# Memory.net
KiCad netlist of a schematic drawn in Altium Designer
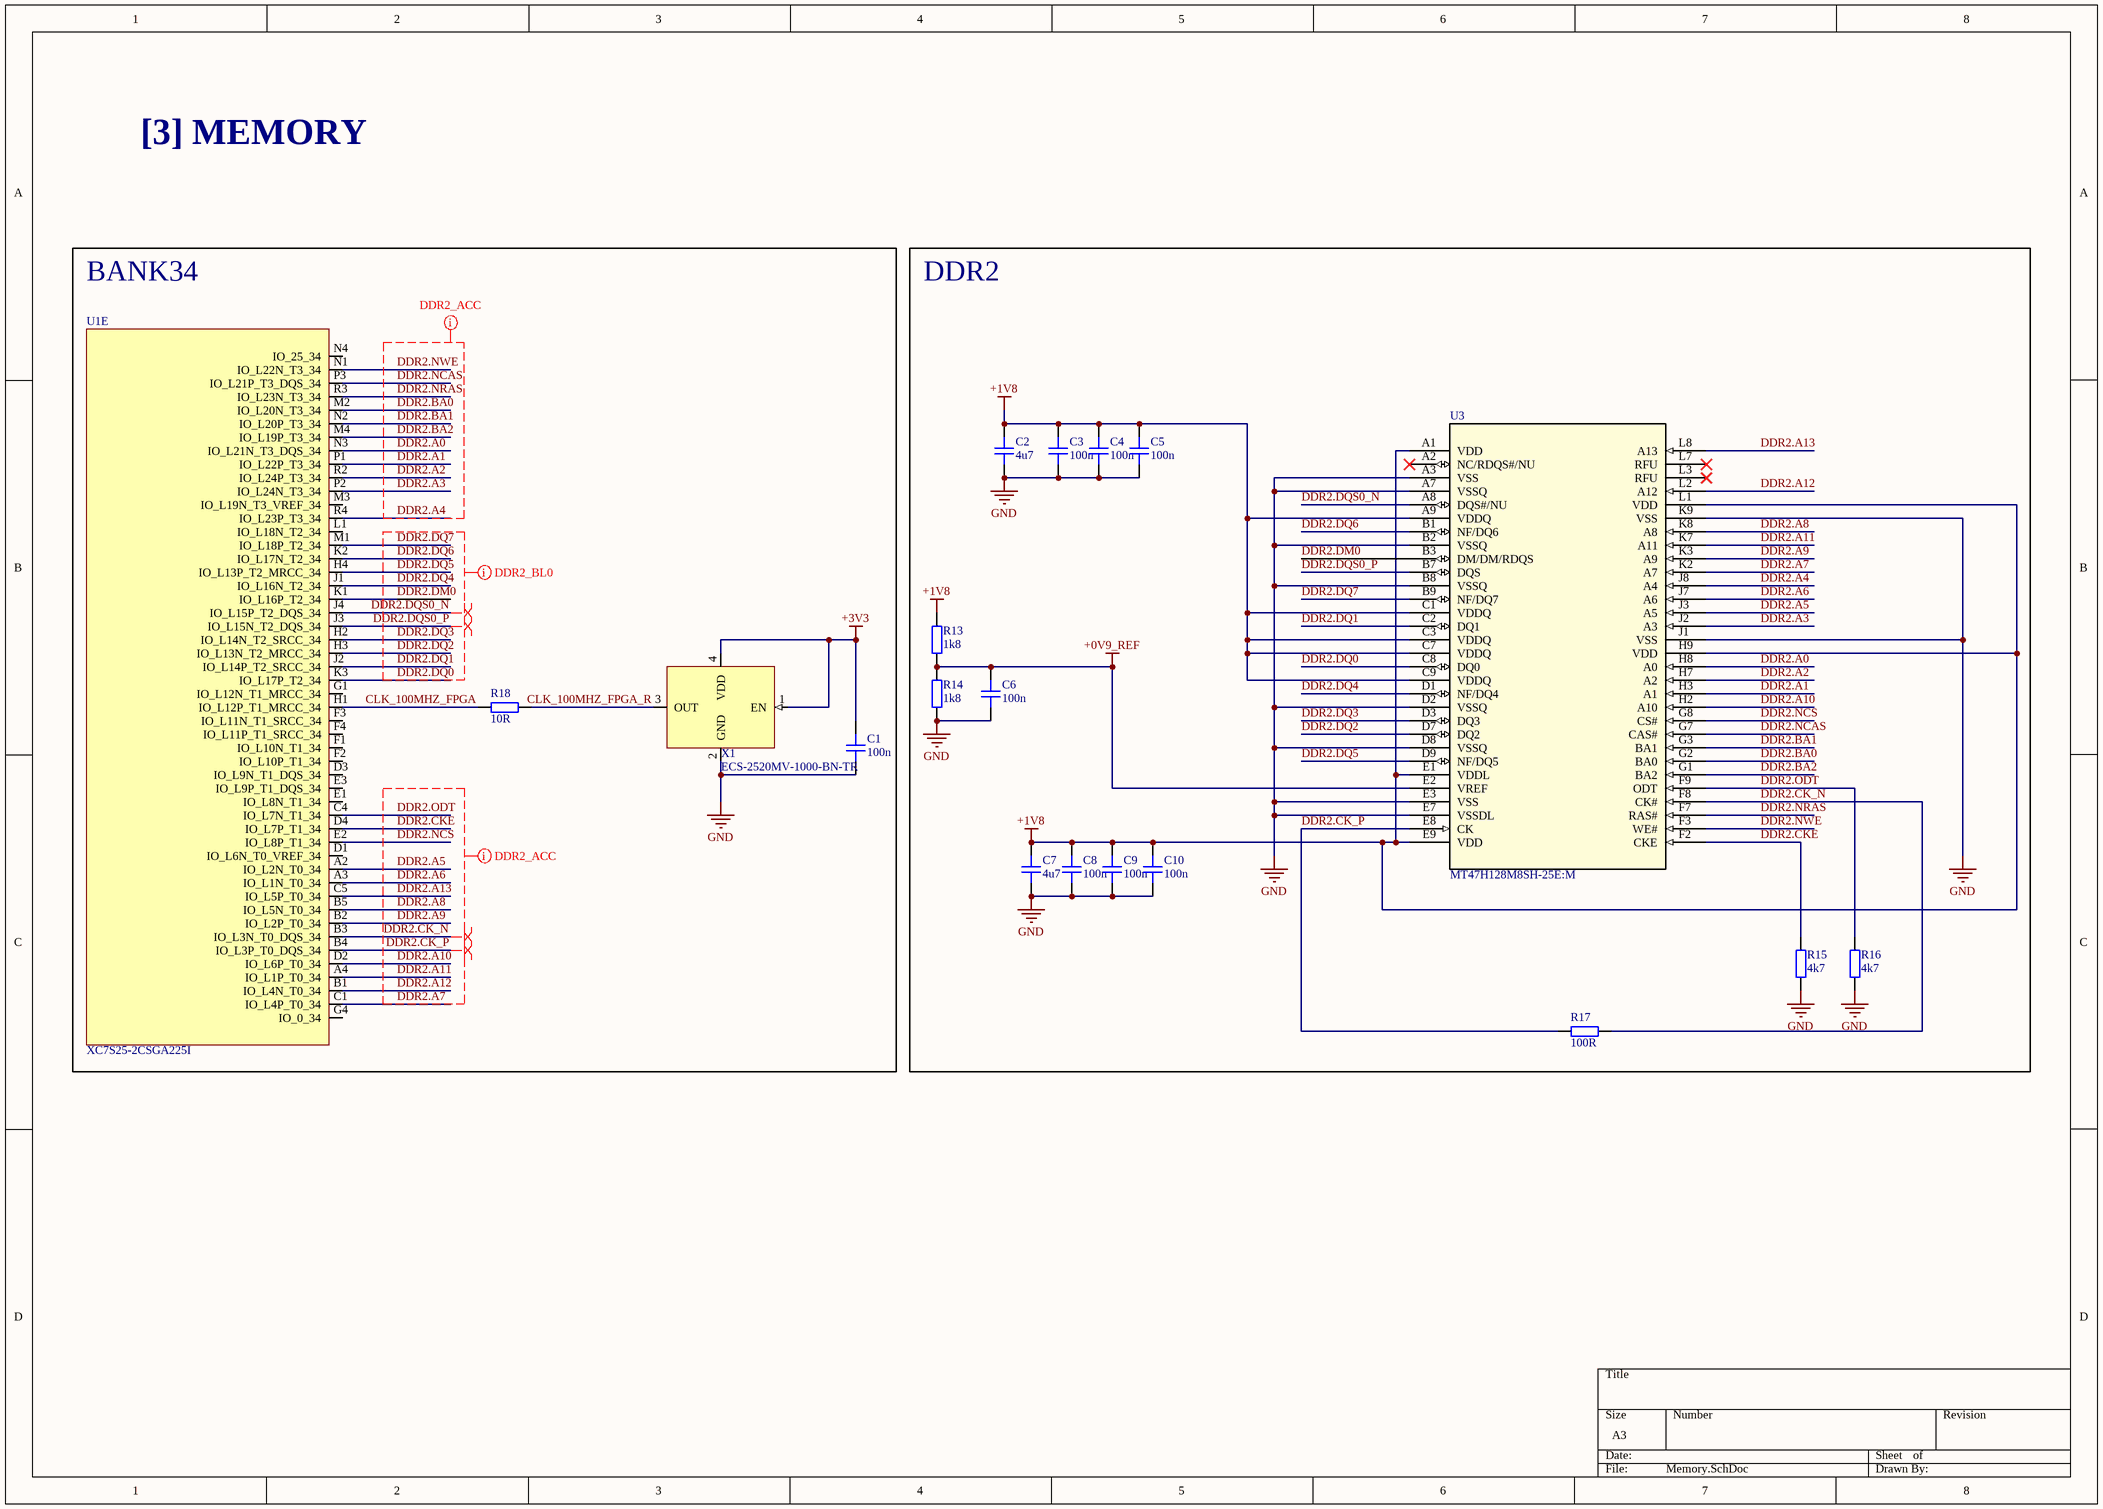
[diagram p0: Memory.SchDoc]

(export (version "E")
  (design (tool "Eeschema 10.0.6"))
  (components
    (comp (ref "C1")
      (value "100n")
      (footprint "CAP_0402")
      (description "Capacitor SMD 0402")
      (libsource (lib "Schematic-Lib-PhilsLab") (part "CAP_0402"))
    )
    (comp (ref "C2")
      (value "4u7")
      (footprint "CAP_0402")
      (description "Capacitor SMD 0402")
      (libsource (lib "Schematic-Lib-PhilsLab") (part "CAP_0402"))
    )
    (comp (ref "C3")
      (value "100n")
      (footprint "CAP_0402")
      (description "Capacitor SMD 0402")
      (libsource (lib "Schematic-Lib-PhilsLab") (part "CAP_0402"))
    )
    (comp (ref "C4")
      (value "100n")
      (footprint "CAP_0402")
      (description "Capacitor SMD 0402")
      (libsource (lib "Schematic-Lib-PhilsLab") (part "CAP_0402"))
    )
    (comp (ref "C5")
      (value "100n")
      (footprint "CAP_0402")
      (description "Capacitor SMD 0402")
      (libsource (lib "Schematic-Lib-PhilsLab") (part "CAP_0402"))
    )
    (comp (ref "C6")
      (value "100n")
      (footprint "CAP_0201")
      (description "Capacitor SMD 0201")
      (libsource (lib "Schematic-Lib-PhilsLab") (part "CAP_0201"))
    )
    (comp (ref "C7")
      (value "4u7")
      (footprint "CAP_0402")
      (description "Capacitor SMD 0402")
      (libsource (lib "Schematic-Lib-PhilsLab") (part "CAP_0402"))
    )
    (comp (ref "C8")
      (value "100n")
      (footprint "CAP_0402")
      (description "Capacitor SMD 0402")
      (libsource (lib "Schematic-Lib-PhilsLab") (part "CAP_0402"))
    )
    (comp (ref "C9")
      (value "100n")
      (footprint "CAP_0402")
      (description "Capacitor SMD 0402")
      (libsource (lib "Schematic-Lib-PhilsLab") (part "CAP_0402"))
    )
    (comp (ref "C10")
      (value "100n")
      (footprint "CAP_0402")
      (description "Capacitor SMD 0402")
      (libsource (lib "Schematic-Lib-PhilsLab") (part "CAP_0402"))
    )
    (comp (ref "R13")
      (value "1k8")
      (footprint "RES_0201")
      (description "Resistor SMD 0201")
      (libsource (lib "Schematic-Lib-PhilsLab") (part "RES_0201"))
    )
    (comp (ref "R14")
      (value "1k8")
      (footprint "RES_0201")
      (description "Resistor SMD 0201")
      (libsource (lib "Schematic-Lib-PhilsLab") (part "RES_0201"))
    )
    (comp (ref "R15")
      (value "4k7")
      (footprint "RES_0402")
      (description "Resistor SMD 0402")
      (libsource (lib "Schematic-Lib-PhilsLab") (part "RES_0402"))
    )
    (comp (ref "R16")
      (value "4k7")
      (footprint "RES_0402")
      (description "Resistor SMD 0402")
      (libsource (lib "Schematic-Lib-PhilsLab") (part "RES_0402"))
    )
    (comp (ref "R17")
      (value "100R")
      (footprint "RES_0201")
      (description "Resistor SMD 0201")
      (libsource (lib "Schematic-Lib-PhilsLab") (part "RES_0201"))
    )
    (comp (ref "R18")
      (value "10R")
      (footprint "RES_0402")
      (description "Resistor SMD 0402")
      (libsource (lib "Schematic-Lib-PhilsLab") (part "RES_0402"))
    )
    (comp (ref "U1")
      (value "XC7S25-2CSGA225I")
      (footprint "CSGA225")
      (fields (field (name "MANUFACTURER") "Xilinx"))
      (libsource (lib "Schematic-Lib-PhilsLab") (part "XC7S25-2CSGA225I"))
    )
    (comp (ref "U3")
      (value "MT47H128M8SH-25E:M")
      (footprint "FBGA60_8X10_MRN")
      (description "No Description Available")
      (libsource (lib "MT47H128M8SH-25E&colon_M") (part "MT47H128M8SH-25E{colon}M"))
    )
    (comp (ref "X1")
      (value "ECS-2520MV-1000-BN-TR")
      (footprint "XTAL_2520")
      (fields
        (field (name "MANUFACTURER") "ECS")
        (field (name "MANUFACTURER PART NUMBER") "ECS-2520MV-130-BN-TR")
      )
      (libsource (lib "Schematic-Lib-PhilsLab") (part "ECS-2520MV-130-BN-TR"))
    )
  )
  (nets
    (net (code "1") (name "+0V9_REF") (class "Default")
      (node (ref "C6") (pin "2") (pinfunction "2_2") (pintype "passive"))
      (node (ref "R13") (pin "1") (pinfunction "1_1") (pintype "passive"))
      (node (ref "R14") (pin "2") (pinfunction "2_2") (pintype "passive"))
      (node (ref "U3") (pin "E2") (pinfunction "VREF_E2") (pintype "power_in"))
    )
    (net (code "2") (name "+1V8") (class "Default")
      (node (ref "C10") (pin "2") (pinfunction "2_2") (pintype "passive"))
      (node (ref "C2") (pin "2") (pinfunction "2_2") (pintype "passive"))
      (node (ref "C3") (pin "2") (pinfunction "2_2") (pintype "passive"))
      (node (ref "C4") (pin "2") (pinfunction "2_2") (pintype "passive"))
      (node (ref "C5") (pin "2") (pinfunction "2_2") (pintype "passive"))
      (node (ref "C7") (pin "2") (pinfunction "2_2") (pintype "passive"))
      (node (ref "C8") (pin "2") (pinfunction "2_2") (pintype "passive"))
      (node (ref "C9") (pin "2") (pinfunction "2_2") (pintype "passive"))
      (node (ref "R13") (pin "2") (pinfunction "2_2") (pintype "passive"))
      (node (ref "U3") (pin "A1") (pinfunction "VDD_A1") (pintype "power_in"))
      (node (ref "U3") (pin "A9") (pinfunction "VDDQ_A9") (pintype "power_in"))
      (node (ref "U3") (pin "C1") (pinfunction "VDDQ_C1") (pintype "power_in"))
      (node (ref "U3") (pin "C3") (pinfunction "VDDQ_C3") (pintype "power_in"))
      (node (ref "U3") (pin "C7") (pinfunction "VDDQ_C7") (pintype "power_in"))
      (node (ref "U3") (pin "C9") (pinfunction "VDDQ_C9") (pintype "power_in"))
      (node (ref "U3") (pin "E1") (pinfunction "VDDL_E1") (pintype "power_in"))
      (node (ref "U3") (pin "E9") (pinfunction "VDD_E9") (pintype "power_in"))
      (node (ref "U3") (pin "H9") (pinfunction "VDD_H9") (pintype "power_in"))
      (node (ref "U3") (pin "L1") (pinfunction "VDD_L1") (pintype "power_in"))
    )
    (net (code "3") (name "+3V3") (class "Default")
      (node (ref "C1") (pin "2") (pinfunction "2_2") (pintype "passive"))
      (node (ref "X1") (pin "1") (pinfunction "EN_1") (pintype "input"))
      (node (ref "X1") (pin "4") (pinfunction "VDD_4") (pintype "power_in"))
    )
    (net (code "4") (name "/CLK_100MHZ_FPGA") (class "Default")
      (node (ref "R18") (pin "2") (pinfunction "2_2") (pintype "passive"))
      (node (ref "U1") (pin "H1") (pinfunction "IO_L12P_T1_MRCC_34_H1") (pintype "bidirectional"))
    )
    (net (code "5") (name "/CLK_100MHZ_FPGA_R") (class "Default")
      (node (ref "R18") (pin "1") (pinfunction "1_1") (pintype "passive"))
      (node (ref "X1") (pin "3") (pinfunction "OUT_3") (pintype "passive"))
    )
    (net (code "6") (name "/DDR2.A0") (class "Default")
      (node (ref "U1") (pin "N3") (pinfunction "IO_L21N_T3_DQS_34_N3") (pintype "bidirectional"))
      (node (ref "U3") (pin "H8") (pinfunction "A0_H8") (pintype "input"))
    )
    (net (code "7") (name "/DDR2.A1") (class "Default")
      (node (ref "U1") (pin "P1") (pinfunction "IO_L22P_T3_34_P1") (pintype "bidirectional"))
      (node (ref "U3") (pin "H3") (pinfunction "A1_H3") (pintype "input"))
    )
    (net (code "8") (name "/DDR2.A2") (class "Default")
      (node (ref "U1") (pin "R2") (pinfunction "IO_L24P_T3_34_R2") (pintype "bidirectional"))
      (node (ref "U3") (pin "H7") (pinfunction "A2_H7") (pintype "input"))
    )
    (net (code "9") (name "/DDR2.A3") (class "Default")
      (node (ref "U1") (pin "P2") (pinfunction "IO_L24N_T3_34_P2") (pintype "bidirectional"))
      (node (ref "U3") (pin "J2") (pinfunction "A3_J2") (pintype "input"))
    )
    (net (code "10") (name "/DDR2.A4") (class "Default")
      (node (ref "U1") (pin "R4") (pinfunction "IO_L23P_T3_34_R4") (pintype "bidirectional"))
      (node (ref "U3") (pin "J8") (pinfunction "A4_J8") (pintype "input"))
    )
    (net (code "11") (name "/DDR2.A5") (class "Default")
      (node (ref "U1") (pin "A2") (pinfunction "IO_L2N_T0_34_A2") (pintype "bidirectional"))
      (node (ref "U3") (pin "J3") (pinfunction "A5_J3") (pintype "input"))
    )
    (net (code "12") (name "/DDR2.A6") (class "Default")
      (node (ref "U1") (pin "A3") (pinfunction "IO_L1N_T0_34_A3") (pintype "bidirectional"))
      (node (ref "U3") (pin "J7") (pinfunction "A6_J7") (pintype "input"))
    )
    (net (code "13") (name "/DDR2.A7") (class "Default")
      (node (ref "U1") (pin "C1") (pinfunction "IO_L4P_T0_34_C1") (pintype "bidirectional"))
      (node (ref "U3") (pin "K2") (pinfunction "A7_K2") (pintype "input"))
    )
    (net (code "14") (name "/DDR2.A8") (class "Default")
      (node (ref "U1") (pin "B5") (pinfunction "IO_L5N_T0_34_B5") (pintype "bidirectional"))
      (node (ref "U3") (pin "K8") (pinfunction "A8_K8") (pintype "input"))
    )
    (net (code "15") (name "/DDR2.A9") (class "Default")
      (node (ref "U1") (pin "B2") (pinfunction "IO_L2P_T0_34_B2") (pintype "bidirectional"))
      (node (ref "U3") (pin "K3") (pinfunction "A9_K3") (pintype "input"))
    )
    (net (code "16") (name "/DDR2.A10") (class "Default")
      (node (ref "U1") (pin "D2") (pinfunction "IO_L6P_T0_34_D2") (pintype "bidirectional"))
      (node (ref "U3") (pin "H2") (pinfunction "A10_H2") (pintype "input"))
    )
    (net (code "17") (name "/DDR2.A11") (class "Default")
      (node (ref "U1") (pin "A4") (pinfunction "IO_L1P_T0_34_A4") (pintype "bidirectional"))
      (node (ref "U3") (pin "K7") (pinfunction "A11_K7") (pintype "input"))
    )
    (net (code "18") (name "/DDR2.A12") (class "Default")
      (node (ref "U1") (pin "B1") (pinfunction "IO_L4N_T0_34_B1") (pintype "bidirectional"))
      (node (ref "U3") (pin "L2") (pinfunction "A12_L2") (pintype "input"))
    )
    (net (code "19") (name "/DDR2.A13") (class "Default")
      (node (ref "U1") (pin "C5") (pinfunction "IO_L5P_T0_34_C5") (pintype "bidirectional"))
      (node (ref "U3") (pin "L8") (pinfunction "A13_L8") (pintype "input"))
    )
    (net (code "20") (name "/DDR2.BA0") (class "Default")
      (node (ref "U1") (pin "M2") (pinfunction "IO_L20N_T3_34_M2") (pintype "bidirectional"))
      (node (ref "U3") (pin "G2") (pinfunction "BA0_G2") (pintype "input"))
    )
    (net (code "21") (name "/DDR2.BA1") (class "Default")
      (node (ref "U1") (pin "N2") (pinfunction "IO_L20P_T3_34_N2") (pintype "bidirectional"))
      (node (ref "U3") (pin "G3") (pinfunction "BA1_G3") (pintype "input"))
    )
    (net (code "22") (name "/DDR2.BA2") (class "Default")
      (node (ref "U1") (pin "M4") (pinfunction "IO_L19P_T3_34_M4") (pintype "bidirectional"))
      (node (ref "U3") (pin "G1") (pinfunction "BA2_G1") (pintype "input"))
    )
    (net (code "23") (name "/DDR2.CKE") (class "Default")
      (node (ref "R15") (pin "2") (pinfunction "2_2") (pintype "passive"))
      (node (ref "U1") (pin "D4") (pinfunction "IO_L7P_T1_34_D4") (pintype "bidirectional"))
      (node (ref "U3") (pin "F2") (pinfunction "CKE_F2") (pintype "input"))
    )
    (net (code "24") (name "/DDR2.CK_N") (class "Default")
      (node (ref "R17") (pin "1") (pinfunction "1_1") (pintype "passive"))
      (node (ref "U1") (pin "B3") (pinfunction "IO_L3N_T0_DQS_34_B3") (pintype "bidirectional"))
      (node (ref "U3") (pin "F8") (pinfunction "CK#_F8") (pintype "input"))
    )
    (net (code "25") (name "/DDR2.CK_P") (class "Default")
      (node (ref "R17") (pin "2") (pinfunction "2_2") (pintype "passive"))
      (node (ref "U1") (pin "B4") (pinfunction "IO_L3P_T0_DQS_34_B4") (pintype "bidirectional"))
      (node (ref "U3") (pin "E8") (pinfunction "CK_E8") (pintype "input"))
    )
    (net (code "26") (name "/DDR2.DM0") (class "Default")
      (node (ref "U1") (pin "K1") (pinfunction "IO_L16P_T2_34_K1") (pintype "bidirectional"))
      (node (ref "U3") (pin "B3") (pinfunction "DM/DM/RDQS_B3") (pintype "bidirectional"))
    )
    (net (code "27") (name "/DDR2.DQ0") (class "Default")
      (node (ref "U1") (pin "K3") (pinfunction "IO_L17P_T2_34_K3") (pintype "bidirectional"))
      (node (ref "U3") (pin "C8") (pinfunction "DQ0_C8") (pintype "bidirectional"))
    )
    (net (code "28") (name "/DDR2.DQ1") (class "Default")
      (node (ref "U1") (pin "J2") (pinfunction "IO_L14P_T2_SRCC_34_J2") (pintype "bidirectional"))
      (node (ref "U3") (pin "C2") (pinfunction "DQ1_C2") (pintype "bidirectional"))
    )
    (net (code "29") (name "/DDR2.DQ2") (class "Default")
      (node (ref "U1") (pin "H3") (pinfunction "IO_L13N_T2_MRCC_34_H3") (pintype "bidirectional"))
      (node (ref "U3") (pin "D7") (pinfunction "DQ2_D7") (pintype "bidirectional"))
    )
    (net (code "30") (name "/DDR2.DQ3") (class "Default")
      (node (ref "U1") (pin "H2") (pinfunction "IO_L14N_T2_SRCC_34_H2") (pintype "bidirectional"))
      (node (ref "U3") (pin "D3") (pinfunction "DQ3_D3") (pintype "bidirectional"))
    )
    (net (code "31") (name "/DDR2.DQ4") (class "Default")
      (node (ref "U1") (pin "J1") (pinfunction "IO_L16N_T2_34_J1") (pintype "bidirectional"))
      (node (ref "U3") (pin "D1") (pinfunction "NF/DQ4_D1") (pintype "bidirectional"))
    )
    (net (code "32") (name "/DDR2.DQ5") (class "Default")
      (node (ref "U1") (pin "H4") (pinfunction "IO_L13P_T2_MRCC_34_H4") (pintype "bidirectional"))
      (node (ref "U3") (pin "D9") (pinfunction "NF/DQ5_D9") (pintype "bidirectional"))
    )
    (net (code "33") (name "/DDR2.DQ6") (class "Default")
      (node (ref "U1") (pin "K2") (pinfunction "IO_L17N_T2_34_K2") (pintype "bidirectional"))
      (node (ref "U3") (pin "B1") (pinfunction "NF/DQ6_B1") (pintype "bidirectional"))
    )
    (net (code "34") (name "/DDR2.DQ7") (class "Default")
      (node (ref "U1") (pin "M1") (pinfunction "IO_L18P_T2_34_M1") (pintype "bidirectional"))
      (node (ref "U3") (pin "B9") (pinfunction "NF/DQ7_B9") (pintype "bidirectional"))
    )
    (net (code "35") (name "/DDR2.DQS0_N") (class "Default")
      (node (ref "U1") (pin "J4") (pinfunction "IO_L15P_T2_DQS_34_J4") (pintype "bidirectional"))
      (node (ref "U3") (pin "A8") (pinfunction "DQS#/NU_A8") (pintype "bidirectional"))
    )
    (net (code "36") (name "/DDR2.DQS0_P") (class "Default")
      (node (ref "U1") (pin "J3") (pinfunction "IO_L15N_T2_DQS_34_J3") (pintype "bidirectional"))
      (node (ref "U3") (pin "B7") (pinfunction "DQS_B7") (pintype "bidirectional"))
    )
    (net (code "37") (name "/DDR2.NCAS") (class "Default")
      (node (ref "U1") (pin "P3") (pinfunction "IO_L21P_T3_DQS_34_P3") (pintype "bidirectional"))
      (node (ref "U3") (pin "G7") (pinfunction "CAS#_G7") (pintype "input"))
    )
    (net (code "38") (name "/DDR2.NCS") (class "Default")
      (node (ref "U1") (pin "E2") (pinfunction "IO_L8P_T1_34_E2") (pintype "bidirectional"))
      (node (ref "U3") (pin "G8") (pinfunction "CS#_G8") (pintype "input"))
    )
    (net (code "39") (name "/DDR2.NRAS") (class "Default")
      (node (ref "U1") (pin "R3") (pinfunction "IO_L23N_T3_34_R3") (pintype "bidirectional"))
      (node (ref "U3") (pin "F7") (pinfunction "RAS#_F7") (pintype "input"))
    )
    (net (code "40") (name "/DDR2.NWE") (class "Default")
      (node (ref "U1") (pin "N1") (pinfunction "IO_L22N_T3_34_N1") (pintype "bidirectional"))
      (node (ref "U3") (pin "F3") (pinfunction "WE#_F3") (pintype "input"))
    )
    (net (code "41") (name "/DDR2.ODT") (class "Default")
      (node (ref "R16") (pin "2") (pinfunction "2_2") (pintype "passive"))
      (node (ref "U1") (pin "C4") (pinfunction "IO_L7N_T1_34_C4") (pintype "bidirectional"))
      (node (ref "U3") (pin "F9") (pinfunction "ODT_F9") (pintype "input"))
    )
    (net (code "42") (name "GND") (class "Default")
      (node (ref "C1") (pin "1") (pinfunction "1_1") (pintype "passive"))
      (node (ref "C10") (pin "1") (pinfunction "1_1") (pintype "passive"))
      (node (ref "C2") (pin "1") (pinfunction "1_1") (pintype "passive"))
      (node (ref "C3") (pin "1") (pinfunction "1_1") (pintype "passive"))
      (node (ref "C4") (pin "1") (pinfunction "1_1") (pintype "passive"))
      (node (ref "C5") (pin "1") (pinfunction "1_1") (pintype "passive"))
      (node (ref "C6") (pin "1") (pinfunction "1_1") (pintype "passive"))
      (node (ref "C7") (pin "1") (pinfunction "1_1") (pintype "passive"))
      (node (ref "C8") (pin "1") (pinfunction "1_1") (pintype "passive"))
      (node (ref "C9") (pin "1") (pinfunction "1_1") (pintype "passive"))
      (node (ref "R14") (pin "1") (pinfunction "1_1") (pintype "passive"))
      (node (ref "R15") (pin "1") (pinfunction "1_1") (pintype "passive"))
      (node (ref "R16") (pin "1") (pinfunction "1_1") (pintype "passive"))
      (node (ref "U3") (pin "A3") (pinfunction "VSS_A3") (pintype "power_in"))
      (node (ref "U3") (pin "A7") (pinfunction "VSSQ_A7") (pintype "power_in"))
      (node (ref "U3") (pin "B2") (pinfunction "VSSQ_B2") (pintype "power_in"))
      (node (ref "U3") (pin "B8") (pinfunction "VSSQ_B8") (pintype "power_in"))
      (node (ref "U3") (pin "D2") (pinfunction "VSSQ_D2") (pintype "power_in"))
      (node (ref "U3") (pin "D8") (pinfunction "VSSQ_D8") (pintype "power_in"))
      (node (ref "U3") (pin "E3") (pinfunction "VSS_E3") (pintype "power_in"))
      (node (ref "U3") (pin "E7") (pinfunction "VSSDL_E7") (pintype "power_in"))
      (node (ref "U3") (pin "J1") (pinfunction "VSS_J1") (pintype "power_in"))
      (node (ref "U3") (pin "K9") (pinfunction "VSS_K9") (pintype "power_in"))
      (node (ref "X1") (pin "2") (pinfunction "GND_2") (pintype "power_in"))
    )
    (net (code "43") (name "unconnected-(U1E-IO_0_34-PadG4)") (class "Default")
      (node (ref "U1") (pin "G4") (pinfunction "IO_0_34_G4") (pintype "bidirectional"))
    )
    (net (code "44") (name "unconnected-(U1E-IO_25_34-PadN4)") (class "Default")
      (node (ref "U1") (pin "N4") (pinfunction "IO_25_34_N4") (pintype "bidirectional"))
    )
    (net (code "45") (name "unconnected-(U1E-IO_L6N_T0_VREF_34-PadD1)") (class "Default")
      (node (ref "U1") (pin "D1") (pinfunction "IO_L6N_T0_VREF_34_D1") (pintype "bidirectional"))
    )
    (net (code "46") (name "unconnected-(U1E-IO_L8N_T1_34-PadE1)") (class "Default")
      (node (ref "U1") (pin "E1") (pinfunction "IO_L8N_T1_34_E1") (pintype "bidirectional"))
    )
    (net (code "47") (name "unconnected-(U1E-IO_L9N_T1_DQS_34-PadD3)") (class "Default")
      (node (ref "U1") (pin "D3") (pinfunction "IO_L9N_T1_DQS_34_D3") (pintype "bidirectional"))
    )
    (net (code "48") (name "unconnected-(U1E-IO_L9P_T1_DQS_34-PadE3)") (class "Default")
      (node (ref "U1") (pin "E3") (pinfunction "IO_L9P_T1_DQS_34_E3") (pintype "bidirectional"))
    )
    (net (code "49") (name "unconnected-(U1E-IO_L10N_T1_34-PadF1)") (class "Default")
      (node (ref "U1") (pin "F1") (pinfunction "IO_L10N_T1_34_F1") (pintype "bidirectional"))
    )
    (net (code "50") (name "unconnected-(U1E-IO_L10P_T1_34-PadF2)") (class "Default")
      (node (ref "U1") (pin "F2") (pinfunction "IO_L10P_T1_34_F2") (pintype "bidirectional"))
    )
    (net (code "51") (name "unconnected-(U1E-IO_L11N_T1_SRCC_34-PadF3)") (class "Default")
      (node (ref "U1") (pin "F3") (pinfunction "IO_L11N_T1_SRCC_34_F3") (pintype "bidirectional"))
    )
    (net (code "52") (name "unconnected-(U1E-IO_L11P_T1_SRCC_34-PadF4)") (class "Default")
      (node (ref "U1") (pin "F4") (pinfunction "IO_L11P_T1_SRCC_34_F4") (pintype "bidirectional"))
    )
    (net (code "53") (name "unconnected-(U1E-IO_L12N_T1_MRCC_34-PadG1)") (class "Default")
      (node (ref "U1") (pin "G1") (pinfunction "IO_L12N_T1_MRCC_34_G1") (pintype "bidirectional"))
    )
    (net (code "54") (name "unconnected-(U1E-IO_L18N_T2_34-PadL1)") (class "Default")
      (node (ref "U1") (pin "L1") (pinfunction "IO_L18N_T2_34_L1") (pintype "bidirectional"))
    )
    (net (code "55") (name "unconnected-(U1E-IO_L19N_T3_VREF_34-PadM3)") (class "Default")
      (node (ref "U1") (pin "M3") (pinfunction "IO_L19N_T3_VREF_34_M3") (pintype "bidirectional"))
    )
    (net (code "56") (name "unconnected-(U3-NC{slash}RDQS#{slash}NU-PadA2)") (class "Default")
      (node (ref "U3") (pin "A2") (pinfunction "NC/RDQS#/NU_A2") (pintype "bidirectional+no_connect"))
    )
    (net (code "57") (name "unconnected-(U3-RFU-PadL3)") (class "Default")
      (node (ref "U3") (pin "L3") (pinfunction "RFU_L3") (pintype "passive+no_connect"))
    )
    (net (code "58") (name "unconnected-(U3-RFU-PadL7)") (class "Default")
      (node (ref "U3") (pin "L7") (pinfunction "RFU_L7") (pintype "passive+no_connect"))
    )
  )
)
